# aKaReZa75_eBoard_USBtoTTL__USBtoTTL__She.net
KiCad netlist of a schematic drawn in Altium Designer
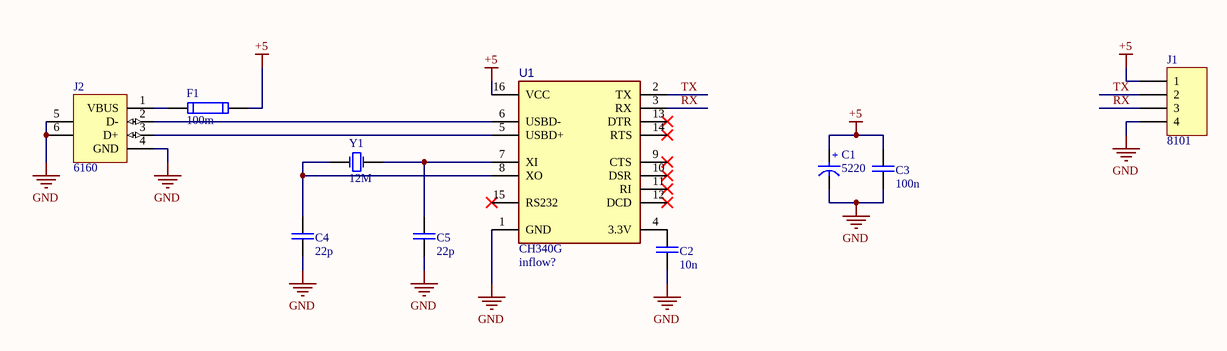
[diagram p0: aKaReZa75_eBoard_USBtoTTL__USBtoTTL__Sheet1.SchDoc]

(export (version "E")
  (design (tool "Eeschema 10.0.6"))
  (components
    (comp (ref "C1")
      (value "10u")
      (footprint "CAP ALUM 5MM")
      (description "Electrolit Capacitor SMD")
      (fields (field (name "INFLOW") "5220") (field (name "VALIDATION") "Valid"))
      (libsource (lib "aKaReZa") (part "Cap_Elec_10u_25_SMD"))
    )
    (comp (ref "C2")
      (value "10n")
      (footprint "CAP 1206/3216")
      (description "Bipolar ceramic capacitor SMD")
      (fields (field (name "VALIDATION") "Valid"))
      (libsource (lib "aKaReZa") (part "Cap_Multi_SMD_1206"))
    )
    (comp (ref "C3")
      (value "100n")
      (footprint "CAP 1206/3216")
      (description "Bipolar ceramic capacitor SMD")
      (fields (field (name "VALIDATION") "Valid"))
      (libsource (lib "aKaReZa") (part "Cap_Multi_SMD_100nF_1206"))
    )
    (comp (ref "C4")
      (value "22p")
      (footprint "CAP 1206/3216")
      (description "Bipolar ceramic capacitor SMD")
      (fields (field (name "VALIDATION") "Valid"))
      (libsource (lib "aKaReZa") (part "Cap_Multi_SMD_1206"))
    )
    (comp (ref "C5")
      (value "22p")
      (footprint "CAP 1206/3216")
      (description "Bipolar ceramic capacitor SMD")
      (fields (field (name "VALIDATION") "Valid"))
      (libsource (lib "aKaReZa") (part "Cap_Multi_SMD_1206"))
    )
    (comp (ref "F1")
      (value "100m")
      (footprint "1206_F")
      (description "Short circiut  protection")
      (fields (field (name "VALIDATION") "Valid"))
      (libsource (lib "aKaReZa") (part "Other_Elec_Fuse_SMD"))
    )
    (comp (ref "J1")
      (value "4")
      (footprint "HDR_THT_4F_2.54mm")
      (description "Header, single row, 4 pin")
      (fields (field (name "INFLOW") "8101") (field (name "VALIDATION") "NT"))
      (libsource (lib "aKaReZa") (part "Con_FPH_4x1_V_THT_2.54"))
    )
    (comp (ref "J2")
      (value "Type A")
      (footprint "USB A TYPE Right Angle")
      (description "USB Connector-A Type")
      (fields (field (name "INFLOW") "6160") (field (name "VALIDATION") "NT"))
      (libsource (lib "aKaReZa") (part "Con_USB2_A"))
    )
    (comp (ref "U1")
      (value "CH340G")
      (footprint "SO16_M")
      (description "TTL To USB Chip")
      (fields (field (name "INFLOW") "inflow?") (field (name "VALIDATION") "Valid"))
      (libsource (lib "aKaReZa") (part "IC_Converter_CH340G"))
    )
    (comp (ref "Y1")
      (value "12M")
      (footprint "Crystal SMD")
      (description "Crystal Oscillator")
      (fields (field (name "VALIDATION") "Valid"))
      (libsource (lib "aKaReZa") (part "Other_Elec_Xtal_SMD"))
    )
  )
  (nets
    (net (code "1") (name "+5") (class "Default")
      (node (ref "C1") (pin "1") (pinfunction "+_1") (pintype "passive"))
      (node (ref "C3") (pin "1") (pinfunction "1_1") (pintype "passive"))
      (node (ref "F1") (pin "2") (pinfunction "2_2") (pintype "passive"))
      (node (ref "J1") (pin "1") (pinfunction "1_1") (pintype "passive"))
      (node (ref "U1") (pin "16") (pinfunction "VCC_16") (pintype "passive"))
    )
    (net (code "2") (name "/RX") (class "Default")
      (node (ref "J1") (pin "3") (pinfunction "3_3") (pintype "passive"))
      (node (ref "U1") (pin "3") (pinfunction "RX_3") (pintype "passive"))
    )
    (net (code "3") (name "/TX") (class "Default")
      (node (ref "J1") (pin "2") (pinfunction "2_2") (pintype "passive"))
      (node (ref "U1") (pin "2") (pinfunction "TX_2") (pintype "passive"))
    )
    (net (code "4") (name "GND") (class "Default")
      (node (ref "C1") (pin "2") (pinfunction "-_2") (pintype "passive"))
      (node (ref "C2") (pin "2") (pinfunction "2_2") (pintype "passive"))
      (node (ref "C3") (pin "2") (pinfunction "2_2") (pintype "passive"))
      (node (ref "C4") (pin "2") (pinfunction "2_2") (pintype "passive"))
      (node (ref "C5") (pin "2") (pinfunction "2_2") (pintype "passive"))
      (node (ref "J1") (pin "4") (pinfunction "4_4") (pintype "passive"))
      (node (ref "J2") (pin "4") (pinfunction "GND_4") (pintype "power_in"))
      (node (ref "J2") (pin "5") (pinfunction "MH_5") (pintype "power_in"))
      (node (ref "J2") (pin "6") (pinfunction "MH_6") (pintype "power_in"))
      (node (ref "U1") (pin "1") (pinfunction "GND_1") (pintype "passive"))
    )
    (net (code "5") (name "Net-(J2-D+)") (class "Default")
      (node (ref "J2") (pin "3") (pinfunction "D+_3") (pintype "bidirectional"))
      (node (ref "U1") (pin "5") (pinfunction "USBD+_5") (pintype "passive"))
    )
    (net (code "6") (name "Net-(J2-D-)") (class "Default")
      (node (ref "J2") (pin "2") (pinfunction "D-_2") (pintype "bidirectional"))
      (node (ref "U1") (pin "6") (pinfunction "USBD-_6") (pintype "passive"))
    )
    (net (code "7") (name "Net-(J2-VBUS)") (class "Default")
      (node (ref "F1") (pin "1") (pinfunction "1_1") (pintype "passive"))
      (node (ref "J2") (pin "1") (pinfunction "VBUS_1") (pintype "power_in"))
    )
    (net (code "8") (name "Net-(U1-3.3V)") (class "Default")
      (node (ref "C2") (pin "1") (pinfunction "1_1") (pintype "passive"))
      (node (ref "U1") (pin "4") (pinfunction "3.3V_4") (pintype "passive"))
    )
    (net (code "9") (name "Net-(U1-XI)") (class "Default")
      (node (ref "C5") (pin "1") (pinfunction "1_1") (pintype "passive"))
      (node (ref "U1") (pin "7") (pinfunction "XI_7") (pintype "passive"))
      (node (ref "Y1") (pin "2") (pinfunction "OSC2_2") (pintype "passive"))
    )
    (net (code "10") (name "Net-(U1-XO)") (class "Default")
      (node (ref "C4") (pin "1") (pinfunction "1_1") (pintype "passive"))
      (node (ref "U1") (pin "8") (pinfunction "XO_8") (pintype "passive"))
      (node (ref "Y1") (pin "1") (pinfunction "OSC1_1") (pintype "passive"))
    )
    (net (code "11") (name "unconnected-(U1-CTS-Pad9)") (class "Default")
      (node (ref "U1") (pin "9") (pinfunction "CTS_9") (pintype "passive+no_connect"))
    )
    (net (code "12") (name "unconnected-(U1-DCD-Pad12)") (class "Default")
      (node (ref "U1") (pin "12") (pinfunction "DCD_12") (pintype "passive+no_connect"))
    )
    (net (code "13") (name "unconnected-(U1-DSR-Pad10)") (class "Default")
      (node (ref "U1") (pin "10") (pinfunction "DSR_10") (pintype "passive+no_connect"))
    )
    (net (code "14") (name "unconnected-(U1-DTR-Pad13)") (class "Default")
      (node (ref "U1") (pin "13") (pinfunction "DTR_13") (pintype "passive+no_connect"))
    )
    (net (code "15") (name "unconnected-(U1-RI-Pad11)") (class "Default")
      (node (ref "U1") (pin "11") (pinfunction "RI_11") (pintype "passive+no_connect"))
    )
    (net (code "16") (name "unconnected-(U1-RS232-Pad15)") (class "Default")
      (node (ref "U1") (pin "15") (pinfunction "RS232_15") (pintype "passive+no_connect"))
    )
    (net (code "17") (name "unconnected-(U1-RTS-Pad14)") (class "Default")
      (node (ref "U1") (pin "14") (pinfunction "RTS_14") (pintype "passive+no_connect"))
    )
  )
)
